# Power_Regulation.net
KiCad netlist of a schematic drawn in Altium Designer
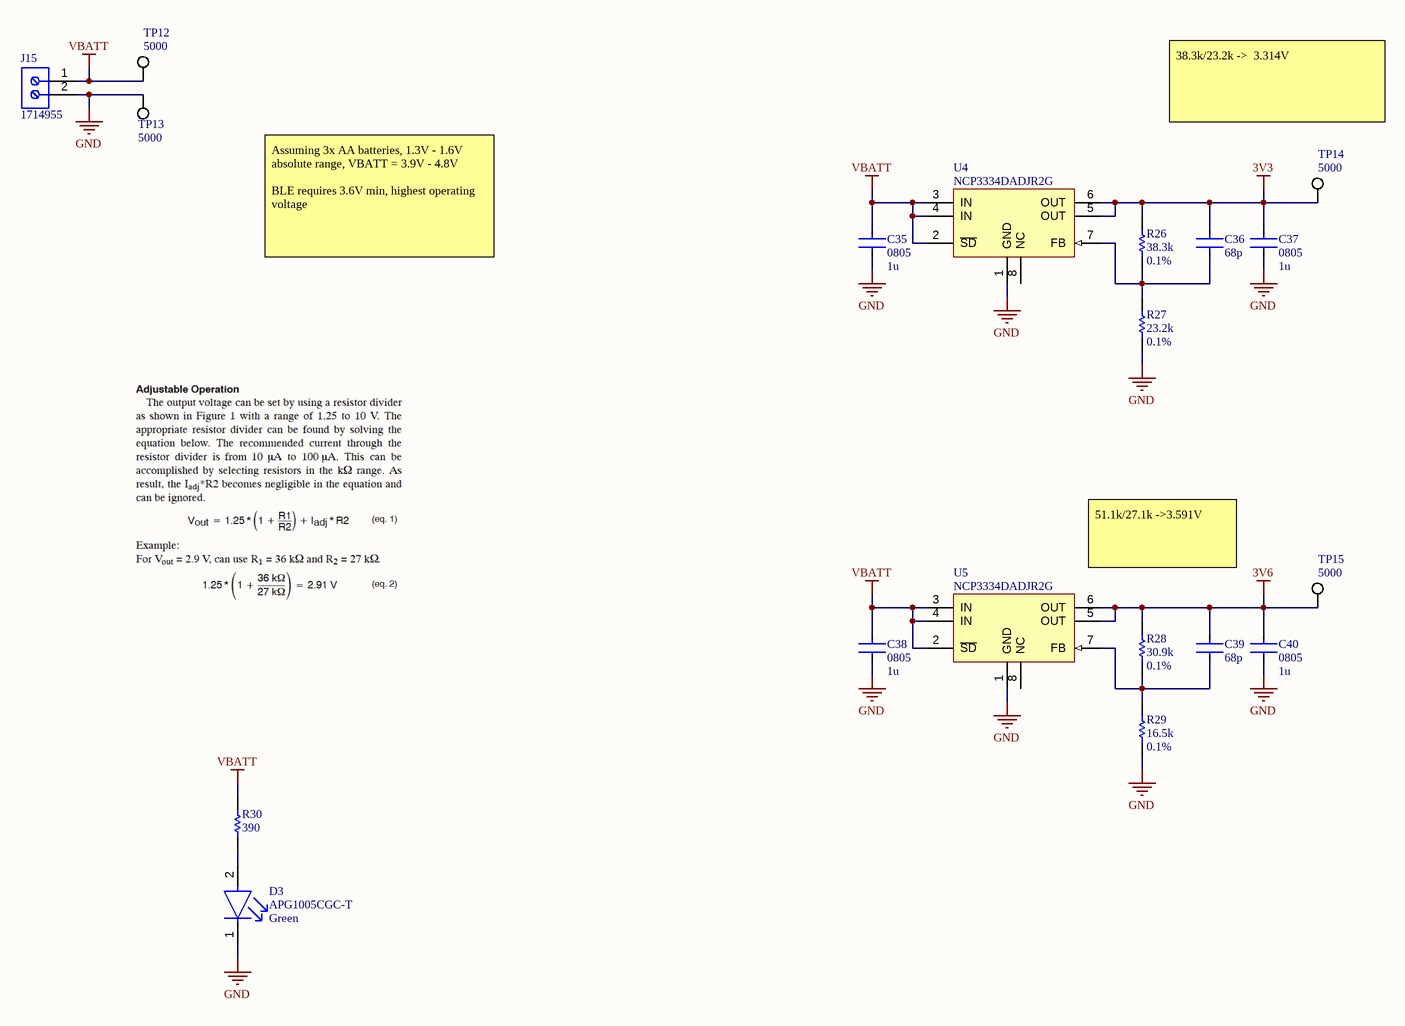
[diagram p0: Power Regulation.SchDoc]

(export (version "E")
  (design (tool "Eeschema 10.0.6"))
  (components
    (comp (ref "C35")
      (value "1u")
      (footprint "FP-0805-Capacitor-CL21-IPC_B")
      (description "CAP CER 50V X7R 0805")
      (fields
        (field (name "TOLERANCE") "0.1")
        (field (name "MANUFACTURER") "KEMET")
        (field (name "PACKAGE") "0805")
      )
      (libsource (lib "CBU-PCB") (part "Ceramic Capacitor 0805"))
    )
    (comp (ref "C36")
      (value "68p")
      (footprint "FP-0603-Capacitor-CL10-IPC_B")
      (description "CAP CER 50V X7R 0603")
      (fields (field (name "TOLERANCE") "0.1") (field (name "MANUFACTURER") "KEMET"))
      (libsource (lib "CBU-PCB") (part "Ceramic Capacitor 0603"))
    )
    (comp (ref "C37")
      (value "1u")
      (footprint "FP-0805-Capacitor-CL21-IPC_B")
      (description "CAP CER 50V X7R 0805")
      (fields
        (field (name "TOLERANCE") "0.1")
        (field (name "MANUFACTURER") "KEMET")
        (field (name "PACKAGE") "0805")
      )
      (libsource (lib "CBU-PCB") (part "Ceramic Capacitor 0805"))
    )
    (comp (ref "C38")
      (value "1u")
      (footprint "FP-0805-Capacitor-CL21-IPC_B")
      (description "CAP CER 50V X7R 0805")
      (fields
        (field (name "TOLERANCE") "0.1")
        (field (name "MANUFACTURER") "KEMET")
        (field (name "PACKAGE") "0805")
      )
      (libsource (lib "CBU-PCB") (part "Ceramic Capacitor 0805"))
    )
    (comp (ref "C39")
      (value "68p")
      (footprint "FP-0603-Capacitor-CL10-IPC_B")
      (description "CAP CER 50V X7R 0603")
      (fields (field (name "TOLERANCE") "0.1") (field (name "MANUFACTURER") "KEMET"))
      (libsource (lib "CBU-PCB") (part "Ceramic Capacitor 0603"))
    )
    (comp (ref "C40")
      (value "1u")
      (footprint "FP-0805-Capacitor-CL21-IPC_B")
      (description "CAP CER 50V X7R 0805")
      (fields
        (field (name "TOLERANCE") "0.1")
        (field (name "MANUFACTURER") "KEMET")
        (field (name "PACKAGE") "0805")
      )
      (libsource (lib "CBU-PCB") (part "Ceramic Capacitor 0805"))
    )
    (comp (ref "D3")
      (value "APG1005CGC-T")
      (footprint "FP-APG1005CGC-T-MFG")
      (description "LED GREEN CLEAR CHIP SMD")
      (fields (field (name "COLOR") "Green"))
      (libsource (lib "CBU-PCB") (part "APG1005CGC-T"))
    )
    (comp (ref "J15")
      (value "1714955")
      (footprint "1714955")
      (description "PC Terminal Block, Pitch 6.35 mm, 1 x 2 Position, Height 21.5 mm, Tail Lenght 5.1 mm, RoHS, Bulk")
      (fields (field (name "MANUFACTURER") "Phoenix Contact"))
      (libsource (lib "CBU-PCB") (part "1714955"))
    )
    (comp (ref "R26")
      (value "38.3k")
      (footprint "RESC1608X55X25NL10T15")
      (fields
        (field (name "TOLERANCE") "0.1%")
        (field (name "MANUFACTURER") "Yageo")
        (field (name "Comment") "RC0603FR-072K2L")
      )
      (libsource (lib "CBU-PCB") (part "Resistor 0603"))
    )
    (comp (ref "R27")
      (value "23.2k")
      (footprint "RESC1608X55X25NL10T15")
      (fields
        (field (name "TOLERANCE") "0.1%")
        (field (name "MANUFACTURER") "Yageo")
        (field (name "Comment") "RC0603FR-072K2L")
      )
      (libsource (lib "CBU-PCB") (part "Resistor 0603"))
    )
    (comp (ref "R28")
      (value "30.9k")
      (footprint "RESC1608X55X25NL10T15")
      (fields
        (field (name "TOLERANCE") "0.1%")
        (field (name "MANUFACTURER") "Yageo")
        (field (name "Comment") "RC0603FR-072K2L")
      )
      (libsource (lib "CBU-PCB") (part "Resistor 0603"))
    )
    (comp (ref "R29")
      (value "16.5k")
      (footprint "RESC1608X55X25NL10T15")
      (fields
        (field (name "TOLERANCE") "0.1%")
        (field (name "MANUFACTURER") "Yageo")
        (field (name "Comment") "RC0603FR-072K2L")
      )
      (libsource (lib "CBU-PCB") (part "Resistor 0603"))
    )
    (comp (ref "R30")
      (value "390")
      (footprint "RESC1608X55X25NL10T15")
      (fields
        (field (name "TOLERANCE") "1%")
        (field (name "MANUFACTURER") "Yageo")
        (field (name "Comment") "RC0603FR-072K2L")
      )
      (libsource (lib "CBU-PCB") (part "Resistor 0603"))
    )
    (comp (ref "TP12")
      (value "5000")
      (footprint "FP-5000-MFG")
      (description "Red PC Test Point, Miniature Phosphor Bronze Silver Plating Through Hole Mounting Type")
      (libsource (lib "CBU-PCB") (part "5000"))
    )
    (comp (ref "TP13")
      (value "5000")
      (footprint "FP-5000-MFG")
      (description "Red PC Test Point, Miniature Phosphor Bronze Silver Plating Through Hole Mounting Type")
      (libsource (lib "CBU-PCB") (part "5000"))
    )
    (comp (ref "TP14")
      (value "5000")
      (footprint "FP-5000-MFG")
      (description "Red PC Test Point, Miniature Phosphor Bronze Silver Plating Through Hole Mounting Type")
      (libsource (lib "CBU-PCB") (part "5000"))
    )
    (comp (ref "TP15")
      (value "5000")
      (footprint "FP-5000-MFG")
      (description "Red PC Test Point, Miniature Phosphor Bronze Silver Plating Through Hole Mounting Type")
      (libsource (lib "CBU-PCB") (part "5000"))
    )
    (comp (ref "U4")
      (value "NCP3334DADJR2G")
      (footprint "NCP3334DADJR2G")
      (description "Linear Voltage Regulator IC Positive Adjustable 1 Output 500mA 8-SOIC")
      (libsource (lib "CBU-PCB") (part "NCP3334DADJR2G"))
    )
    (comp (ref "U5")
      (value "NCP3334DADJR2G")
      (footprint "NCP3334DADJR2G")
      (description "Linear Voltage Regulator IC Positive Adjustable 1 Output 500mA 8-SOIC")
      (libsource (lib "CBU-PCB") (part "NCP3334DADJR2G"))
    )
  )
  (nets
    (net (code "1") (name "3V3") (class "Default")
      (node (ref "C36") (pin "1") (pinfunction "1_1") (pintype "passive"))
      (node (ref "C37") (pin "1") (pinfunction "1_1") (pintype "passive"))
      (node (ref "R26") (pin "2") (pinfunction "2_2") (pintype "passive"))
      (node (ref "TP14") (pin "1") (pinfunction "1_1") (pintype "passive"))
      (node (ref "U4") (pin "5") (pinfunction "OUT_5") (pintype "power_in"))
      (node (ref "U4") (pin "6") (pinfunction "OUT_6") (pintype "power_in"))
    )
    (net (code "2") (name "3V6") (class "Default")
      (node (ref "C39") (pin "1") (pinfunction "1_1") (pintype "passive"))
      (node (ref "C40") (pin "1") (pinfunction "1_1") (pintype "passive"))
      (node (ref "R28") (pin "2") (pinfunction "2_2") (pintype "passive"))
      (node (ref "TP15") (pin "1") (pinfunction "1_1") (pintype "passive"))
      (node (ref "U5") (pin "5") (pinfunction "OUT_5") (pintype "power_in"))
      (node (ref "U5") (pin "6") (pinfunction "OUT_6") (pintype "power_in"))
    )
    (net (code "3") (name "GND") (class "Default")
      (node (ref "C35") (pin "2") (pinfunction "2_2") (pintype "passive"))
      (node (ref "C37") (pin "2") (pinfunction "2_2") (pintype "passive"))
      (node (ref "C38") (pin "2") (pinfunction "2_2") (pintype "passive"))
      (node (ref "C40") (pin "2") (pinfunction "2_2") (pintype "passive"))
      (node (ref "D3") (pin "1") (pinfunction "C_1") (pintype "passive"))
      (node (ref "J15") (pin "2") (pinfunction "2_2") (pintype "passive"))
      (node (ref "R27") (pin "1") (pinfunction "1_1") (pintype "passive"))
      (node (ref "R29") (pin "1") (pinfunction "1_1") (pintype "passive"))
      (node (ref "TP13") (pin "1") (pinfunction "1_1") (pintype "passive"))
      (node (ref "U4") (pin "1") (pinfunction "GND_1") (pintype "power_in"))
      (node (ref "U5") (pin "1") (pinfunction "GND_1") (pintype "power_in"))
    )
    (net (code "4") (name "Net-(D3-A)") (class "Default")
      (node (ref "D3") (pin "2") (pinfunction "A_2") (pintype "passive"))
      (node (ref "R30") (pin "1") (pinfunction "1_1") (pintype "passive"))
    )
    (net (code "5") (name "Net-(U4-FB)") (class "Default")
      (node (ref "C36") (pin "2") (pinfunction "2_2") (pintype "passive"))
      (node (ref "R26") (pin "1") (pinfunction "1_1") (pintype "passive"))
      (node (ref "R27") (pin "2") (pinfunction "2_2") (pintype "passive"))
      (node (ref "U4") (pin "7") (pinfunction "FB_7") (pintype "input"))
    )
    (net (code "6") (name "Net-(U5-FB)") (class "Default")
      (node (ref "C39") (pin "2") (pinfunction "2_2") (pintype "passive"))
      (node (ref "R28") (pin "1") (pinfunction "1_1") (pintype "passive"))
      (node (ref "R29") (pin "2") (pinfunction "2_2") (pintype "passive"))
      (node (ref "U5") (pin "7") (pinfunction "FB_7") (pintype "input"))
    )
    (net (code "7") (name "VBATT") (class "Default")
      (node (ref "C35") (pin "1") (pinfunction "1_1") (pintype "passive"))
      (node (ref "C38") (pin "1") (pinfunction "1_1") (pintype "passive"))
      (node (ref "J15") (pin "1") (pinfunction "1_1") (pintype "passive"))
      (node (ref "R30") (pin "2") (pinfunction "2_2") (pintype "passive"))
      (node (ref "TP12") (pin "1") (pinfunction "1_1") (pintype "passive"))
      (node (ref "U4") (pin "2") (pinfunction "~{SD}_2") (pintype "power_in"))
      (node (ref "U4") (pin "3") (pinfunction "IN_3") (pintype "power_in"))
      (node (ref "U4") (pin "4") (pinfunction "IN_4") (pintype "power_in"))
      (node (ref "U5") (pin "2") (pinfunction "~{SD}_2") (pintype "power_in"))
      (node (ref "U5") (pin "3") (pinfunction "IN_3") (pintype "power_in"))
      (node (ref "U5") (pin "4") (pinfunction "IN_4") (pintype "power_in"))
    )
    (net (code "8") (name "unconnected-(U4-NC-Pad8)") (class "Default")
      (node (ref "U4") (pin "8") (pinfunction "NC_8") (pintype "passive"))
    )
    (net (code "9") (name "unconnected-(U5-NC-Pad8)") (class "Default")
      (node (ref "U5") (pin "8") (pinfunction "NC_8") (pintype "passive"))
    )
  )
)
